# 07_ZYNQ_DDR.net
KiCad netlist of a schematic drawn in Altium Designer
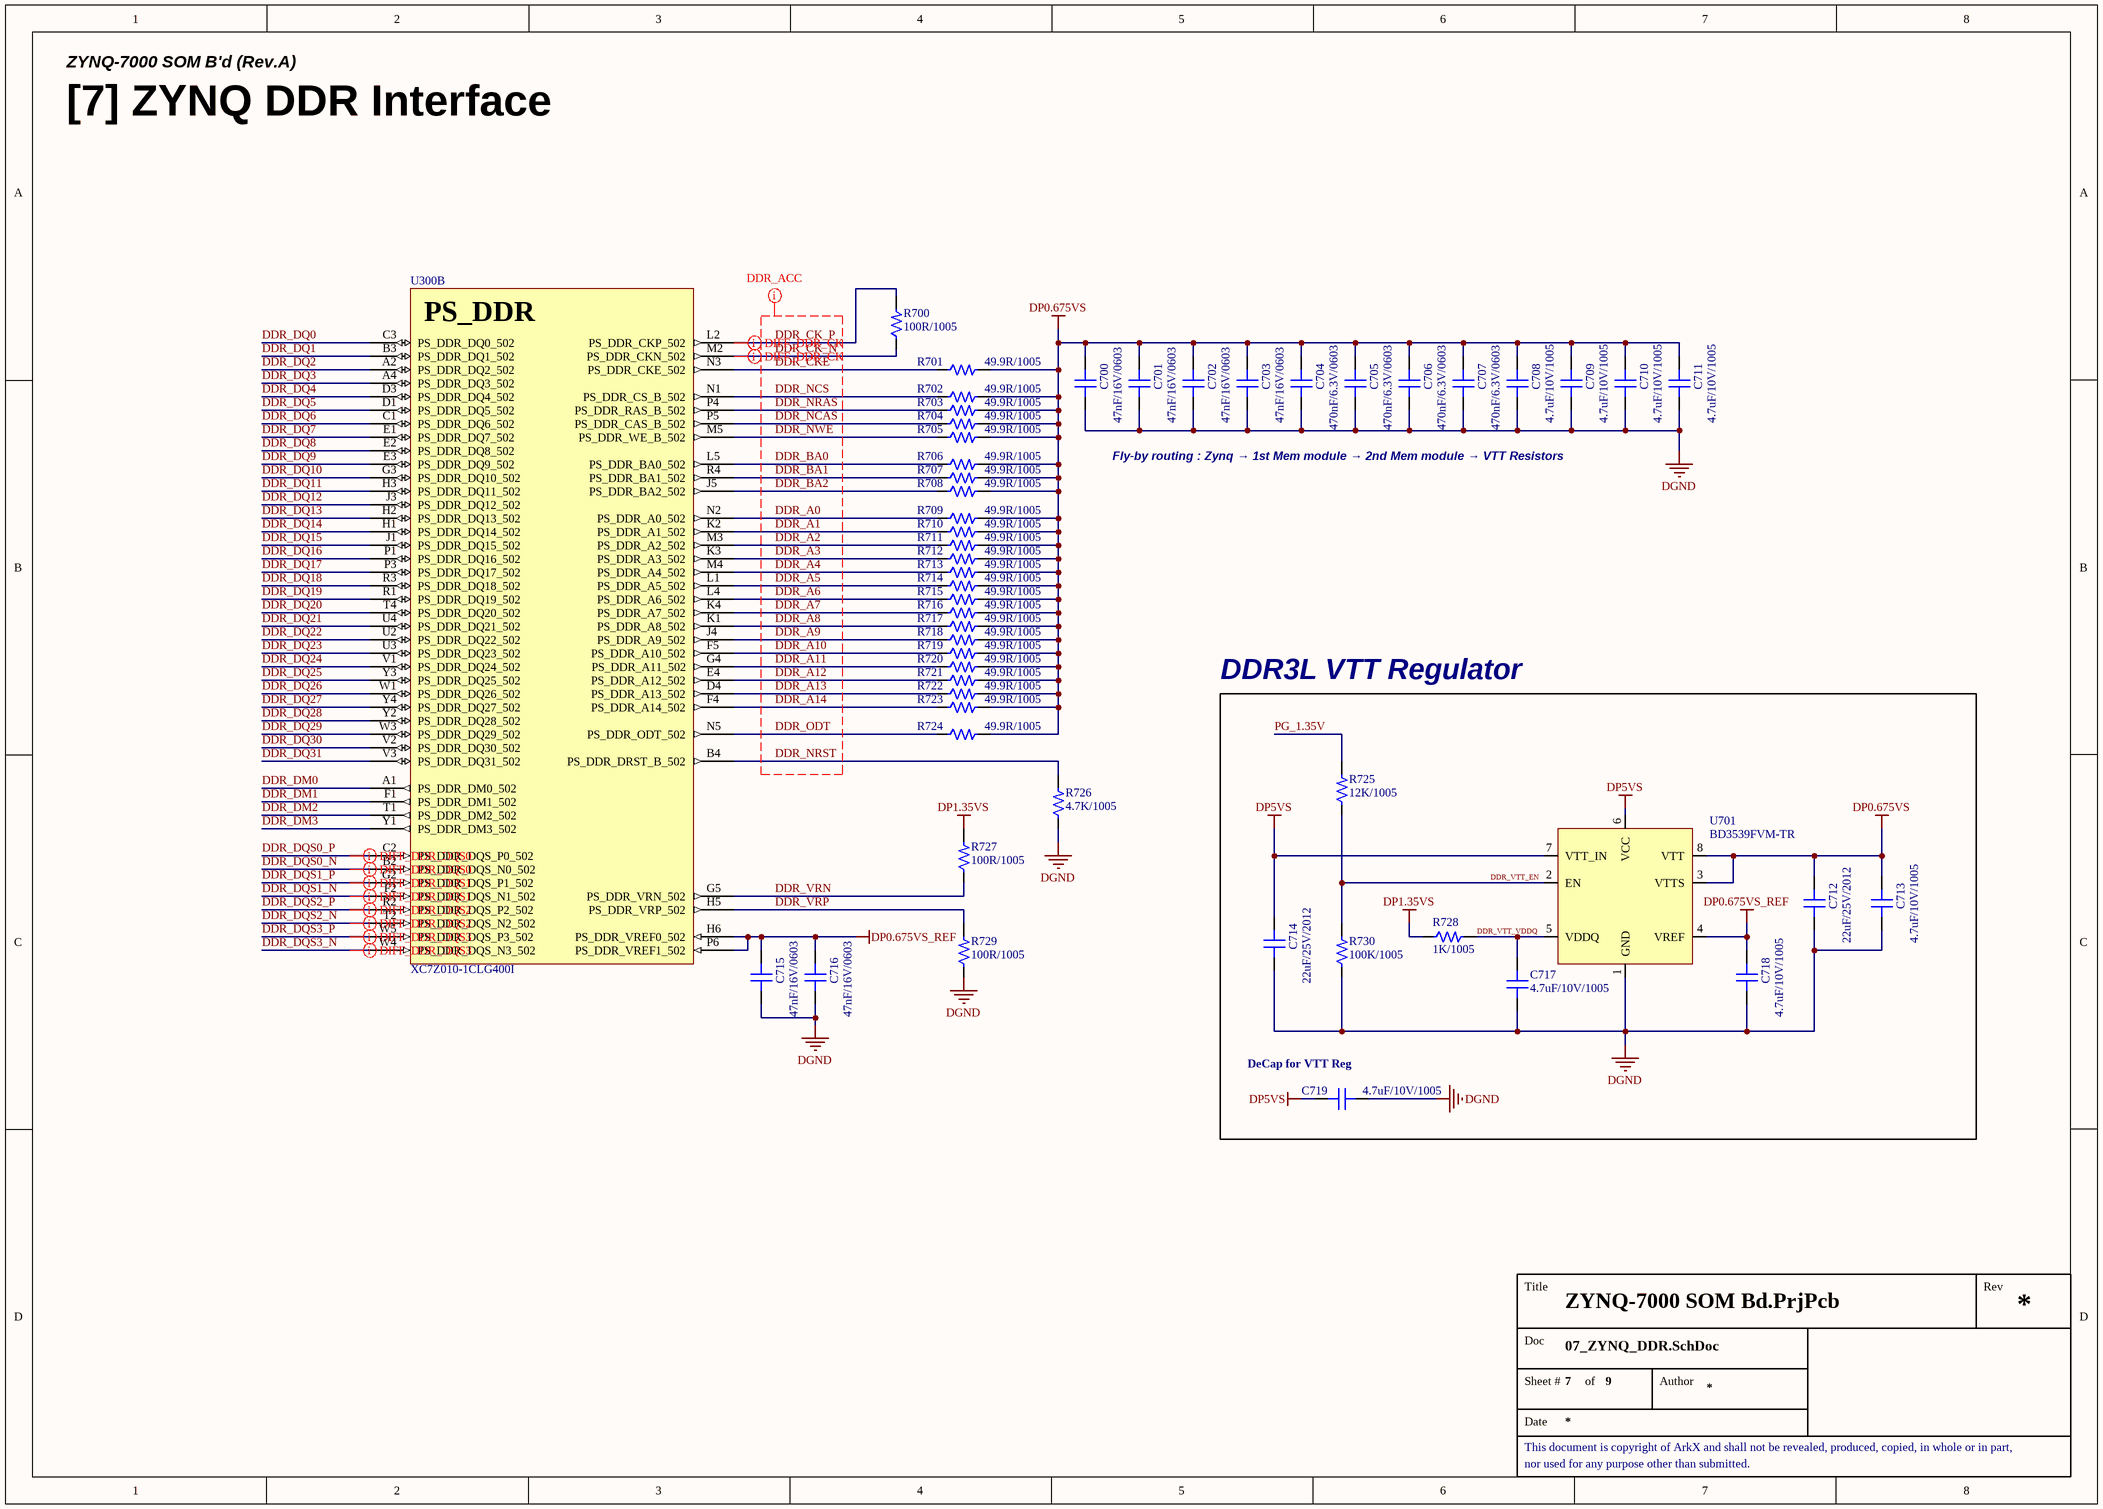
[diagram p0: 07_ZYNQ_DDR.SchDoc]

(export (version "E")
  (design (tool "Eeschema 10.0.6"))
  (components
    (comp (ref "C700")
      (value "47nF/16V/0603")
      (footprint "CAP 0603 (0201_INCH)")
      (description "16V 47nF X5R ±10% 0201 Multilayer Ceramic Capacitors MLCC - SMD/SMT ROHS")
      (fields (field (name "LCSC PART #") "C88917"))
      (libsource (lib "Arkx") (part "CAP_47nF/16V/0603"))
    )
    (comp (ref "C701")
      (value "47nF/16V/0603")
      (footprint "CAP 0603 (0201_INCH)")
      (description "16V 47nF X5R ±10% 0201 Multilayer Ceramic Capacitors MLCC - SMD/SMT ROHS")
      (fields (field (name "LCSC PART #") "C88917"))
      (libsource (lib "Arkx") (part "CAP_47nF/16V/0603"))
    )
    (comp (ref "C702")
      (value "47nF/16V/0603")
      (footprint "CAP 0603 (0201_INCH)")
      (description "16V 47nF X5R ±10% 0201 Multilayer Ceramic Capacitors MLCC - SMD/SMT ROHS")
      (fields (field (name "LCSC PART #") "C88917"))
      (libsource (lib "Arkx") (part "CAP_47nF/16V/0603"))
    )
    (comp (ref "C703")
      (value "47nF/16V/0603")
      (footprint "CAP 0603 (0201_INCH)")
      (description "16V 47nF X5R ±10% 0201 Multilayer Ceramic Capacitors MLCC - SMD/SMT ROHS")
      (fields (field (name "LCSC PART #") "C88917"))
      (libsource (lib "Arkx") (part "CAP_47nF/16V/0603"))
    )
    (comp (ref "C704")
      (value "470nF/6.3V/0603")
      (footprint "CAP 0603 (0201_INCH)")
      (description "6.3V 470nF X5R ±10% 0201  Multilayer Ceramic Capacitors MLCC - SMD/SMT ROHS")
      (fields (field (name "LCSC PART #") "C85926"))
      (libsource (lib "Arkx") (part "CAP_470nF/6.3V/0603"))
    )
    (comp (ref "C705")
      (value "470nF/6.3V/0603")
      (footprint "CAP 0603 (0201_INCH)")
      (description "6.3V 470nF X5R ±10% 0201  Multilayer Ceramic Capacitors MLCC - SMD/SMT ROHS")
      (fields (field (name "LCSC PART #") "C85926"))
      (libsource (lib "Arkx") (part "CAP_470nF/6.3V/0603"))
    )
    (comp (ref "C706")
      (value "470nF/6.3V/0603")
      (footprint "CAP 0603 (0201_INCH)")
      (description "6.3V 470nF X5R ±10% 0201  Multilayer Ceramic Capacitors MLCC - SMD/SMT ROHS")
      (fields (field (name "LCSC PART #") "C85926"))
      (libsource (lib "Arkx") (part "CAP_470nF/6.3V/0603"))
    )
    (comp (ref "C707")
      (value "470nF/6.3V/0603")
      (footprint "CAP 0603 (0201_INCH)")
      (description "6.3V 470nF X5R ±10% 0201  Multilayer Ceramic Capacitors MLCC - SMD/SMT ROHS")
      (fields (field (name "LCSC PART #") "C85926"))
      (libsource (lib "Arkx") (part "CAP_470nF/6.3V/0603"))
    )
    (comp (ref "C708")
      (value "4.7uF/10V/1005")
      (footprint "CAP 1005 (0402_INCH)")
      (description "10V 4.7uF X5R ±20% 0402  Multilayer Ceramic Capacitors MLCC - SMD/SMT ROHS")
      (fields (field (name "LCSC PART #") "C23733"))
      (libsource (lib "Arkx") (part "CAP_4.7uF/10V/1005"))
    )
    (comp (ref "C709")
      (value "4.7uF/10V/1005")
      (footprint "CAP 1005 (0402_INCH)")
      (description "10V 4.7uF X5R ±20% 0402  Multilayer Ceramic Capacitors MLCC - SMD/SMT ROHS")
      (fields (field (name "LCSC PART #") "C23733"))
      (libsource (lib "Arkx") (part "CAP_4.7uF/10V/1005"))
    )
    (comp (ref "C710")
      (value "4.7uF/10V/1005")
      (footprint "CAP 1005 (0402_INCH)")
      (description "10V 4.7uF X5R ±20% 0402  Multilayer Ceramic Capacitors MLCC - SMD/SMT ROHS")
      (fields (field (name "LCSC PART #") "C23733"))
      (libsource (lib "Arkx") (part "CAP_4.7uF/10V/1005"))
    )
    (comp (ref "C711")
      (value "4.7uF/10V/1005")
      (footprint "CAP 1005 (0402_INCH)")
      (description "10V 4.7uF X5R ±20% 0402  Multilayer Ceramic Capacitors MLCC - SMD/SMT ROHS")
      (fields (field (name "LCSC PART #") "C23733"))
      (libsource (lib "Arkx") (part "CAP_4.7uF/10V/1005"))
    )
    (comp (ref "C712")
      (value "22uF/25V/2012")
      (footprint "CAP 2012 (0805_INCH)")
      (description "Ceramic CAP_22uF/25V/2012")
      (fields (field (name "LCSC PART #") "C45783"))
      (libsource (lib "Arkx") (part "CAP_22uF/25V/2012"))
    )
    (comp (ref "C713")
      (value "4.7uF/10V/1005")
      (footprint "CAP 1005 (0402_INCH)")
      (description "10V 4.7uF X5R ±20% 0402  Multilayer Ceramic Capacitors MLCC - SMD/SMT ROHS")
      (fields (field (name "LCSC PART #") "C23733"))
      (libsource (lib "Arkx") (part "CAP_4.7uF/10V/1005"))
    )
    (comp (ref "C714")
      (value "22uF/25V/2012")
      (footprint "CAP 2012 (0805_INCH)")
      (description "Ceramic CAP_22uF/25V/2012")
      (fields (field (name "LCSC PART #") "C45783"))
      (libsource (lib "Arkx") (part "CAP_22uF/25V/2012"))
    )
    (comp (ref "C715")
      (value "47nF/16V/0603")
      (footprint "CAP 0603 (0201_INCH)")
      (description "16V 47nF X5R ±10% 0201 Multilayer Ceramic Capacitors MLCC - SMD/SMT ROHS")
      (fields (field (name "LCSC PART #") "C88917"))
      (libsource (lib "Arkx") (part "CAP_47nF/16V/0603"))
    )
    (comp (ref "C716")
      (value "47nF/16V/0603")
      (footprint "CAP 0603 (0201_INCH)")
      (description "16V 47nF X5R ±10% 0201 Multilayer Ceramic Capacitors MLCC - SMD/SMT ROHS")
      (fields (field (name "LCSC PART #") "C88917"))
      (libsource (lib "Arkx") (part "CAP_47nF/16V/0603"))
    )
    (comp (ref "C717")
      (value "4.7uF/10V/1005")
      (footprint "CAP 1005 (0402_INCH)")
      (description "10V 4.7uF X5R ±20% 0402  Multilayer Ceramic Capacitors MLCC - SMD/SMT ROHS")
      (fields (field (name "LCSC PART #") "C23733"))
      (libsource (lib "Arkx") (part "CAP_4.7uF/10V/1005"))
    )
    (comp (ref "C718")
      (value "4.7uF/10V/1005")
      (footprint "CAP 1005 (0402_INCH)")
      (description "10V 4.7uF X5R ±20% 0402  Multilayer Ceramic Capacitors MLCC - SMD/SMT ROHS")
      (fields (field (name "LCSC PART #") "C23733"))
      (libsource (lib "Arkx") (part "CAP_4.7uF/10V/1005"))
    )
    (comp (ref "C719")
      (value "4.7uF/10V/1005")
      (footprint "CAP 1005 (0402_INCH)")
      (description "10V 4.7uF X5R ±20% 0402  Multilayer Ceramic Capacitors MLCC - SMD/SMT ROHS")
      (fields (field (name "LCSC PART #") "C23733"))
      (libsource (lib "Arkx") (part "CAP_4.7uF/10V/1005"))
    )
    (comp (ref "R700")
      (value "100R/1005")
      (footprint "RES 1005 (0402_inch)")
      (description "RES_100R/1005/62.5mW")
      (fields (field (name "LCSC PART #") "C25076"))
      (libsource (lib "Arkx") (part "RES_100R/1005/62.5mW"))
    )
    (comp (ref "R701")
      (value "49.9R/1005")
      (footprint "RES 1005 (0402_inch)")
      (description "RES_49.9R/1005/62.5mW")
      (fields (field (name "LCSC PART #") "C25120"))
      (libsource (lib "Arkx") (part "RES_49.9R/1005/62.5mW"))
    )
    (comp (ref "R702")
      (value "49.9R/1005")
      (footprint "RES 1005 (0402_inch)")
      (description "RES_49.9R/1005/62.5mW")
      (fields (field (name "LCSC PART #") "C25120"))
      (libsource (lib "Arkx") (part "RES_49.9R/1005/62.5mW"))
    )
    (comp (ref "R703")
      (value "49.9R/1005")
      (footprint "RES 1005 (0402_inch)")
      (description "RES_49.9R/1005/62.5mW")
      (fields (field (name "LCSC PART #") "C25120"))
      (libsource (lib "Arkx") (part "RES_49.9R/1005/62.5mW"))
    )
    (comp (ref "R704")
      (value "49.9R/1005")
      (footprint "RES 1005 (0402_inch)")
      (description "RES_49.9R/1005/62.5mW")
      (fields (field (name "LCSC PART #") "C25120"))
      (libsource (lib "Arkx") (part "RES_49.9R/1005/62.5mW"))
    )
    (comp (ref "R705")
      (value "49.9R/1005")
      (footprint "RES 1005 (0402_inch)")
      (description "RES_49.9R/1005/62.5mW")
      (fields (field (name "LCSC PART #") "C25120"))
      (libsource (lib "Arkx") (part "RES_49.9R/1005/62.5mW"))
    )
    (comp (ref "R706")
      (value "49.9R/1005")
      (footprint "RES 1005 (0402_inch)")
      (description "RES_49.9R/1005/62.5mW")
      (fields (field (name "LCSC PART #") "C25120"))
      (libsource (lib "Arkx") (part "RES_49.9R/1005/62.5mW"))
    )
    (comp (ref "R707")
      (value "49.9R/1005")
      (footprint "RES 1005 (0402_inch)")
      (description "RES_49.9R/1005/62.5mW")
      (fields (field (name "LCSC PART #") "C25120"))
      (libsource (lib "Arkx") (part "RES_49.9R/1005/62.5mW"))
    )
    (comp (ref "R708")
      (value "49.9R/1005")
      (footprint "RES 1005 (0402_inch)")
      (description "RES_49.9R/1005/62.5mW")
      (fields (field (name "LCSC PART #") "C25120"))
      (libsource (lib "Arkx") (part "RES_49.9R/1005/62.5mW"))
    )
    (comp (ref "R709")
      (value "49.9R/1005")
      (footprint "RES 1005 (0402_inch)")
      (description "RES_49.9R/1005/62.5mW")
      (fields (field (name "LCSC PART #") "C25120"))
      (libsource (lib "Arkx") (part "RES_49.9R/1005/62.5mW"))
    )
    (comp (ref "R710")
      (value "49.9R/1005")
      (footprint "RES 1005 (0402_inch)")
      (description "RES_49.9R/1005/62.5mW")
      (fields (field (name "LCSC PART #") "C25120"))
      (libsource (lib "Arkx") (part "RES_49.9R/1005/62.5mW"))
    )
    (comp (ref "R711")
      (value "49.9R/1005")
      (footprint "RES 1005 (0402_inch)")
      (description "RES_49.9R/1005/62.5mW")
      (fields (field (name "LCSC PART #") "C25120"))
      (libsource (lib "Arkx") (part "RES_49.9R/1005/62.5mW"))
    )
    (comp (ref "R712")
      (value "49.9R/1005")
      (footprint "RES 1005 (0402_inch)")
      (description "RES_49.9R/1005/62.5mW")
      (fields (field (name "LCSC PART #") "C25120"))
      (libsource (lib "Arkx") (part "RES_49.9R/1005/62.5mW"))
    )
    (comp (ref "R713")
      (value "49.9R/1005")
      (footprint "RES 1005 (0402_inch)")
      (description "RES_49.9R/1005/62.5mW")
      (fields (field (name "LCSC PART #") "C25120"))
      (libsource (lib "Arkx") (part "RES_49.9R/1005/62.5mW"))
    )
    (comp (ref "R714")
      (value "49.9R/1005")
      (footprint "RES 1005 (0402_inch)")
      (description "RES_49.9R/1005/62.5mW")
      (fields (field (name "LCSC PART #") "C25120"))
      (libsource (lib "Arkx") (part "RES_49.9R/1005/62.5mW"))
    )
    (comp (ref "R715")
      (value "49.9R/1005")
      (footprint "RES 1005 (0402_inch)")
      (description "RES_49.9R/1005/62.5mW")
      (fields (field (name "LCSC PART #") "C25120"))
      (libsource (lib "Arkx") (part "RES_49.9R/1005/62.5mW"))
    )
    (comp (ref "R716")
      (value "49.9R/1005")
      (footprint "RES 1005 (0402_inch)")
      (description "RES_49.9R/1005/62.5mW")
      (fields (field (name "LCSC PART #") "C25120"))
      (libsource (lib "Arkx") (part "RES_49.9R/1005/62.5mW"))
    )
    (comp (ref "R717")
      (value "49.9R/1005")
      (footprint "RES 1005 (0402_inch)")
      (description "RES_49.9R/1005/62.5mW")
      (fields (field (name "LCSC PART #") "C25120"))
      (libsource (lib "Arkx") (part "RES_49.9R/1005/62.5mW"))
    )
    (comp (ref "R718")
      (value "49.9R/1005")
      (footprint "RES 1005 (0402_inch)")
      (description "RES_49.9R/1005/62.5mW")
      (fields (field (name "LCSC PART #") "C25120"))
      (libsource (lib "Arkx") (part "RES_49.9R/1005/62.5mW"))
    )
    (comp (ref "R719")
      (value "49.9R/1005")
      (footprint "RES 1005 (0402_inch)")
      (description "RES_49.9R/1005/62.5mW")
      (fields (field (name "LCSC PART #") "C25120"))
      (libsource (lib "Arkx") (part "RES_49.9R/1005/62.5mW"))
    )
    (comp (ref "R720")
      (value "49.9R/1005")
      (footprint "RES 1005 (0402_inch)")
      (description "RES_49.9R/1005/62.5mW")
      (fields (field (name "LCSC PART #") "C25120"))
      (libsource (lib "Arkx") (part "RES_49.9R/1005/62.5mW"))
    )
    (comp (ref "R721")
      (value "49.9R/1005")
      (footprint "RES 1005 (0402_inch)")
      (description "RES_49.9R/1005/62.5mW")
      (fields (field (name "LCSC PART #") "C25120"))
      (libsource (lib "Arkx") (part "RES_49.9R/1005/62.5mW"))
    )
    (comp (ref "R722")
      (value "49.9R/1005")
      (footprint "RES 1005 (0402_inch)")
      (description "RES_49.9R/1005/62.5mW")
      (fields (field (name "LCSC PART #") "C25120"))
      (libsource (lib "Arkx") (part "RES_49.9R/1005/62.5mW"))
    )
    (comp (ref "R723")
      (value "49.9R/1005")
      (footprint "RES 1005 (0402_inch)")
      (description "RES_49.9R/1005/62.5mW")
      (fields (field (name "LCSC PART #") "C25120"))
      (libsource (lib "Arkx") (part "RES_49.9R/1005/62.5mW"))
    )
    (comp (ref "R724")
      (value "49.9R/1005")
      (footprint "RES 1005 (0402_inch)")
      (description "RES_49.9R/1005/62.5mW")
      (fields (field (name "LCSC PART #") "C25120"))
      (libsource (lib "Arkx") (part "RES_49.9R/1005/62.5mW"))
    )
    (comp (ref "R725")
      (value "12K/1005")
      (footprint "RES 1005 (0402_inch)")
      (description "RES_12K/1005/62.5mW")
      (fields (field (name "LCSC PART #") "C25752"))
      (libsource (lib "Arkx") (part "RES_12K/1005/62.5mW"))
    )
    (comp (ref "R726")
      (value "4.7K/1005")
      (footprint "RES 1005 (0402_inch)")
      (description "RES_4.7K/1005/62.5mW")
      (fields (field (name "LCSC PART #") "C25900"))
      (libsource (lib "Arkx") (part "RES_4.7K/1005/62.5mW"))
    )
    (comp (ref "R727")
      (value "100R/1005")
      (footprint "RES 1005 (0402_inch)")
      (description "RES_100R/1005/62.5mW")
      (fields (field (name "LCSC PART #") "C25076"))
      (libsource (lib "Arkx") (part "RES_100R/1005/62.5mW"))
    )
    (comp (ref "R728")
      (value "1K/1005")
      (footprint "RES 1005 (0402_inch)")
      (description "RES_1K/1005/62.5mW")
      (fields (field (name "LCSC PART #") "C11702"))
      (libsource (lib "Arkx") (part "RES_1K/1005/62.5mW"))
    )
    (comp (ref "R729")
      (value "100R/1005")
      (footprint "RES 1005 (0402_inch)")
      (description "RES_100R/1005/62.5mW")
      (fields (field (name "LCSC PART #") "C25076"))
      (libsource (lib "Arkx") (part "RES_100R/1005/62.5mW"))
    )
    (comp (ref "R730")
      (value "100K/1005")
      (footprint "RES 1005 (0402_inch)")
      (description "RES_100K/1005/62.5mW")
      (fields (field (name "LCSC PART #") "C25741"))
      (libsource (lib "Arkx") (part "RES_100K/1005/62.5mW"))
    )
    (comp (ref "U300")
      (value "XC7Z010-1CLG400I")
      (footprint "IC_SOC_XC7Z010-1CLG400I")
      (fields (field (name "LCSC PART #") "C2840994"))
      (libsource (lib "Arkx") (part "IC_SOC_XC7Z010-1CLG400I"))
    )
    (comp (ref "U701")
      (value "BD3539FVM-TR")
      (footprint "IC_MSOP-8")
      (description "1.0V to 5.5V, 1A 1ch\r\nTermination Regulators for DDR-SDRAMs, 8-MSOP")
      (fields (field (name "LCSC PART #") "C213437"))
      (libsource (lib "Arkx") (part "IC_REG_VTT_BD3539FVM-TR"))
    )
  )
  (nets
    (net (code "1") (name "/DDR_A0") (class "Default")
      (node (ref "R709") (pin "1") (pinfunction "1_1") (pintype "passive"))
      (node (ref "U300") (pin "N2") (pinfunction "PS_DDR_A0_502_N2") (pintype "output"))
    )
    (net (code "2") (name "/DDR_A1") (class "Default")
      (node (ref "R710") (pin "1") (pinfunction "1_1") (pintype "passive"))
      (node (ref "U300") (pin "K2") (pinfunction "PS_DDR_A1_502_K2") (pintype "output"))
    )
    (net (code "3") (name "/DDR_A2") (class "Default")
      (node (ref "R711") (pin "1") (pinfunction "1_1") (pintype "passive"))
      (node (ref "U300") (pin "M3") (pinfunction "PS_DDR_A2_502_M3") (pintype "output"))
    )
    (net (code "4") (name "/DDR_A3") (class "Default")
      (node (ref "R712") (pin "1") (pinfunction "1_1") (pintype "passive"))
      (node (ref "U300") (pin "K3") (pinfunction "PS_DDR_A3_502_K3") (pintype "output"))
    )
    (net (code "5") (name "/DDR_A4") (class "Default")
      (node (ref "R713") (pin "1") (pinfunction "1_1") (pintype "passive"))
      (node (ref "U300") (pin "M4") (pinfunction "PS_DDR_A4_502_M4") (pintype "output"))
    )
    (net (code "6") (name "/DDR_A5") (class "Default")
      (node (ref "R714") (pin "1") (pinfunction "1_1") (pintype "passive"))
      (node (ref "U300") (pin "L1") (pinfunction "PS_DDR_A5_502_L1") (pintype "output"))
    )
    (net (code "7") (name "/DDR_A6") (class "Default")
      (node (ref "R715") (pin "1") (pinfunction "1_1") (pintype "passive"))
      (node (ref "U300") (pin "L4") (pinfunction "PS_DDR_A6_502_L4") (pintype "output"))
    )
    (net (code "8") (name "/DDR_A7") (class "Default")
      (node (ref "R716") (pin "1") (pinfunction "1_1") (pintype "passive"))
      (node (ref "U300") (pin "K4") (pinfunction "PS_DDR_A7_502_K4") (pintype "output"))
    )
    (net (code "9") (name "/DDR_A8") (class "Default")
      (node (ref "R717") (pin "1") (pinfunction "1_1") (pintype "passive"))
      (node (ref "U300") (pin "K1") (pinfunction "PS_DDR_A8_502_K1") (pintype "output"))
    )
    (net (code "10") (name "/DDR_A9") (class "Default")
      (node (ref "R718") (pin "1") (pinfunction "1_1") (pintype "passive"))
      (node (ref "U300") (pin "J4") (pinfunction "PS_DDR_A9_502_J4") (pintype "output"))
    )
    (net (code "11") (name "/DDR_A10") (class "Default")
      (node (ref "R719") (pin "1") (pinfunction "1_1") (pintype "passive"))
      (node (ref "U300") (pin "F5") (pinfunction "PS_DDR_A10_502_F5") (pintype "output"))
    )
    (net (code "12") (name "/DDR_A11") (class "Default")
      (node (ref "R720") (pin "1") (pinfunction "1_1") (pintype "passive"))
      (node (ref "U300") (pin "G4") (pinfunction "PS_DDR_A11_502_G4") (pintype "output"))
    )
    (net (code "13") (name "/DDR_A12") (class "Default")
      (node (ref "R721") (pin "1") (pinfunction "1_1") (pintype "passive"))
      (node (ref "U300") (pin "E4") (pinfunction "PS_DDR_A12_502_E4") (pintype "output"))
    )
    (net (code "14") (name "/DDR_A13") (class "Default")
      (node (ref "R722") (pin "1") (pinfunction "1_1") (pintype "passive"))
      (node (ref "U300") (pin "D4") (pinfunction "PS_DDR_A13_502_D4") (pintype "output"))
    )
    (net (code "15") (name "/DDR_A14") (class "Default")
      (node (ref "R723") (pin "1") (pinfunction "1_1") (pintype "passive"))
      (node (ref "U300") (pin "F4") (pinfunction "PS_DDR_A14_502_F4") (pintype "output"))
    )
    (net (code "16") (name "/DDR_BA0") (class "Default")
      (node (ref "R706") (pin "1") (pinfunction "1_1") (pintype "passive"))
      (node (ref "U300") (pin "L5") (pinfunction "PS_DDR_BA0_502_L5") (pintype "output"))
    )
    (net (code "17") (name "/DDR_BA1") (class "Default")
      (node (ref "R707") (pin "1") (pinfunction "1_1") (pintype "passive"))
      (node (ref "U300") (pin "R4") (pinfunction "PS_DDR_BA1_502_R4") (pintype "output"))
    )
    (net (code "18") (name "/DDR_BA2") (class "Default")
      (node (ref "R708") (pin "1") (pinfunction "1_1") (pintype "passive"))
      (node (ref "U300") (pin "J5") (pinfunction "PS_DDR_BA2_502_J5") (pintype "output"))
    )
    (net (code "19") (name "/DDR_CKE") (class "Default")
      (node (ref "R701") (pin "1") (pinfunction "1_1") (pintype "passive"))
      (node (ref "U300") (pin "N3") (pinfunction "PS_DDR_CKE_502_N3") (pintype "output"))
    )
    (net (code "20") (name "/DDR_CK_N") (class "Default")
      (node (ref "R700") (pin "1") (pinfunction "1_1") (pintype "passive"))
      (node (ref "U300") (pin "M2") (pinfunction "PS_DDR_CKN_502_M2") (pintype "output"))
    )
    (net (code "21") (name "/DDR_CK_P") (class "Default")
      (node (ref "R700") (pin "2") (pinfunction "2_2") (pintype "passive"))
      (node (ref "U300") (pin "L2") (pinfunction "PS_DDR_CKP_502_L2") (pintype "output"))
    )
    (net (code "22") (name "/DDR_DM0") (class "Default")
      (node (ref "U300") (pin "A1") (pinfunction "PS_DDR_DM0_502_A1") (pintype "output"))
    )
    (net (code "23") (name "/DDR_DM1") (class "Default")
      (node (ref "U300") (pin "F1") (pinfunction "PS_DDR_DM1_502_F1") (pintype "output"))
    )
    (net (code "24") (name "/DDR_DM2") (class "Default")
      (node (ref "U300") (pin "T1") (pinfunction "PS_DDR_DM2_502_T1") (pintype "output"))
    )
    (net (code "25") (name "/DDR_DM3") (class "Default")
      (node (ref "U300") (pin "Y1") (pinfunction "PS_DDR_DM3_502_Y1") (pintype "output"))
    )
    (net (code "26") (name "/DDR_DQ0") (class "Default")
      (node (ref "U300") (pin "C3") (pinfunction "PS_DDR_DQ0_502_C3") (pintype "bidirectional"))
    )
    (net (code "27") (name "/DDR_DQ1") (class "Default")
      (node (ref "U300") (pin "B3") (pinfunction "PS_DDR_DQ1_502_B3") (pintype "bidirectional"))
    )
    (net (code "28") (name "/DDR_DQ2") (class "Default")
      (node (ref "U300") (pin "A2") (pinfunction "PS_DDR_DQ2_502_A2") (pintype "bidirectional"))
    )
    (net (code "29") (name "/DDR_DQ3") (class "Default")
      (node (ref "U300") (pin "A4") (pinfunction "PS_DDR_DQ3_502_A4") (pintype "bidirectional"))
    )
    (net (code "30") (name "/DDR_DQ4") (class "Default")
      (node (ref "U300") (pin "D3") (pinfunction "PS_DDR_DQ4_502_D3") (pintype "bidirectional"))
    )
    (net (code "31") (name "/DDR_DQ5") (class "Default")
      (node (ref "U300") (pin "D1") (pinfunction "PS_DDR_DQ5_502_D1") (pintype "bidirectional"))
    )
    (net (code "32") (name "/DDR_DQ6") (class "Default")
      (node (ref "U300") (pin "C1") (pinfunction "PS_DDR_DQ6_502_C1") (pintype "bidirectional"))
    )
    (net (code "33") (name "/DDR_DQ7") (class "Default")
      (node (ref "U300") (pin "E1") (pinfunction "PS_DDR_DQ7_502_E1") (pintype "bidirectional"))
    )
    (net (code "34") (name "/DDR_DQ8") (class "Default")
      (node (ref "U300") (pin "E2") (pinfunction "PS_DDR_DQ8_502_E2") (pintype "bidirectional"))
    )
    (net (code "35") (name "/DDR_DQ9") (class "Default")
      (node (ref "U300") (pin "E3") (pinfunction "PS_DDR_DQ9_502_E3") (pintype "bidirectional"))
    )
    (net (code "36") (name "/DDR_DQ10") (class "Default")
      (node (ref "U300") (pin "G3") (pinfunction "PS_DDR_DQ10_502_G3") (pintype "bidirectional"))
    )
    (net (code "37") (name "/DDR_DQ11") (class "Default")
      (node (ref "U300") (pin "H3") (pinfunction "PS_DDR_DQ11_502_H3") (pintype "bidirectional"))
    )
    (net (code "38") (name "/DDR_DQ12") (class "Default")
      (node (ref "U300") (pin "J3") (pinfunction "PS_DDR_DQ12_502_J3") (pintype "bidirectional"))
    )
    (net (code "39") (name "/DDR_DQ13") (class "Default")
      (node (ref "U300") (pin "H2") (pinfunction "PS_DDR_DQ13_502_H2") (pintype "bidirectional"))
    )
    (net (code "40") (name "/DDR_DQ14") (class "Default")
      (node (ref "U300") (pin "H1") (pinfunction "PS_DDR_DQ14_502_H1") (pintype "bidirectional"))
    )
    (net (code "41") (name "/DDR_DQ15") (class "Default")
      (node (ref "U300") (pin "J1") (pinfunction "PS_DDR_DQ15_502_J1") (pintype "bidirectional"))
    )
    (net (code "42") (name "/DDR_DQ16") (class "Default")
      (node (ref "U300") (pin "P1") (pinfunction "PS_DDR_DQ16_502_P1") (pintype "bidirectional"))
    )
    (net (code "43") (name "/DDR_DQ17") (class "Default")
      (node (ref "U300") (pin "P3") (pinfunction "PS_DDR_DQ17_502_P3") (pintype "bidirectional"))
    )
    (net (code "44") (name "/DDR_DQ18") (class "Default")
      (node (ref "U300") (pin "R3") (pinfunction "PS_DDR_DQ18_502_R3") (pintype "bidirectional"))
    )
    (net (code "45") (name "/DDR_DQ19") (class "Default")
      (node (ref "U300") (pin "R1") (pinfunction "PS_DDR_DQ19_502_R1") (pintype "bidirectional"))
    )
    (net (code "46") (name "/DDR_DQ20") (class "Default")
      (node (ref "U300") (pin "T4") (pinfunction "PS_DDR_DQ20_502_T4") (pintype "bidirectional"))
    )
    (net (code "47") (name "/DDR_DQ21") (class "Default")
      (node (ref "U300") (pin "U4") (pinfunction "PS_DDR_DQ21_502_U4") (pintype "bidirectional"))
    )
    (net (code "48") (name "/DDR_DQ22") (class "Default")
      (node (ref "U300") (pin "U2") (pinfunction "PS_DDR_DQ22_502_U2") (pintype "bidirectional"))
    )
    (net (code "49") (name "/DDR_DQ23") (class "Default")
      (node (ref "U300") (pin "U3") (pinfunction "PS_DDR_DQ23_502_U3") (pintype "bidirectional"))
    )
    (net (code "50") (name "/DDR_DQ24") (class "Default")
      (node (ref "U300") (pin "V1") (pinfunction "PS_DDR_DQ24_502_V1") (pintype "bidirectional"))
    )
    (net (code "51") (name "/DDR_DQ25") (class "Default")
      (node (ref "U300") (pin "Y3") (pinfunction "PS_DDR_DQ25_502_Y3") (pintype "bidirectional"))
    )
    (net (code "52") (name "/DDR_DQ26") (class "Default")
      (node (ref "U300") (pin "W1") (pinfunction "PS_DDR_DQ26_502_W1") (pintype "bidirectional"))
    )
    (net (code "53") (name "/DDR_DQ27") (class "Default")
      (node (ref "U300") (pin "Y4") (pinfunction "PS_DDR_DQ27_502_Y4") (pintype "bidirectional"))
    )
    (net (code "54") (name "/DDR_DQ28") (class "Default")
      (node (ref "U300") (pin "Y2") (pinfunction "PS_DDR_DQ28_502_Y2") (pintype "bidirectional"))
    )
    (net (code "55") (name "/DDR_DQ29") (class "Default")
      (node (ref "U300") (pin "W3") (pinfunction "PS_DDR_DQ29_502_W3") (pintype "bidirectional"))
    )
    (net (code "56") (name "/DDR_DQ30") (class "Default")
      (node (ref "U300") (pin "V2") (pinfunction "PS_DDR_DQ30_502_V2") (pintype "bidirectional"))
    )
    (net (code "57") (name "/DDR_DQ31") (class "Default")
      (node (ref "U300") (pin "V3") (pinfunction "PS_DDR_DQ31_502_V3") (pintype "bidirectional"))
    )
    (net (code "58") (name "/DDR_DQS0_N") (class "Default")
      (node (ref "U300") (pin "B2") (pinfunction "PS_DDR_DQS_N0_502_B2") (pintype "input"))
    )
    (net (code "59") (name "/DDR_DQS0_P") (class "Default")
      (node (ref "U300") (pin "C2") (pinfunction "PS_DDR_DQS_P0_502_C2") (pintype "input"))
    )
    (net (code "60") (name "/DDR_DQS1_N") (class "Default")
      (node (ref "U300") (pin "F2") (pinfunction "PS_DDR_DQS_N1_502_F2") (pintype "input"))
    )
    (net (code "61") (name "/DDR_DQS1_P") (class "Default")
      (node (ref "U300") (pin "G2") (pinfunction "PS_DDR_DQS_P1_502_G2") (pintype "input"))
    )
    (net (code "62") (name "/DDR_DQS2_N") (class "Default")
      (node (ref "U300") (pin "T2") (pinfunction "PS_DDR_DQS_N2_502_T2") (pintype "input"))
    )
    (net (code "63") (name "/DDR_DQS2_P") (class "Default")
      (node (ref "U300") (pin "R2") (pinfunction "PS_DDR_DQS_P2_502_R2") (pintype "input"))
    )
    (net (code "64") (name "/DDR_DQS3_N") (class "Default")
      (node (ref "U300") (pin "W4") (pinfunction "PS_DDR_DQS_N3_502_W4") (pintype "input"))
    )
    (net (code "65") (name "/DDR_DQS3_P") (class "Default")
      (node (ref "U300") (pin "W5") (pinfunction "PS_DDR_DQS_P3_502_W5") (pintype "input"))
    )
    (net (code "66") (name "/DDR_NCAS") (class "Default")
      (node (ref "R704") (pin "1") (pinfunction "1_1") (pintype "passive"))
      (node (ref "U300") (pin "P5") (pinfunction "PS_DDR_CAS_B_502_P5") (pintype "output"))
    )
    (net (code "67") (name "/DDR_NCS") (class "Default")
      (node (ref "R702") (pin "1") (pinfunction "1_1") (pintype "passive"))
      (node (ref "U300") (pin "N1") (pinfunction "PS_DDR_CS_B_502_N1") (pintype "output"))
    )
    (net (code "68") (name "/DDR_NRAS") (class "Default")
      (node (ref "R703") (pin "1") (pinfunction "1_1") (pintype "passive"))
      (node (ref "U300") (pin "P4") (pinfunction "PS_DDR_RAS_B_502_P4") (pintype "output"))
    )
    (net (code "69") (name "/DDR_NRST") (class "Default")
      (node (ref "R726") (pin "2") (pinfunction "2_2") (pintype "passive"))
      (node (ref "U300") (pin "B4") (pinfunction "PS_DDR_DRST_B_502_B4") (pintype "output"))
    )
    (net (code "70") (name "/DDR_NWE") (class "Default")
      (node (ref "R705") (pin "1") (pinfunction "1_1") (pintype "passive"))
      (node (ref "U300") (pin "M5") (pinfunction "PS_DDR_WE_B_502_M5") (pintype "output"))
    )
    (net (code "71") (name "/DDR_ODT") (class "Default")
      (node (ref "R724") (pin "1") (pinfunction "1_1") (pintype "passive"))
      (node (ref "U300") (pin "N5") (pinfunction "PS_DDR_ODT_502_N5") (pintype "output"))
    )
    (net (code "72") (name "/DDR_VRN") (class "Default")
      (node (ref "R727") (pin "1") (pinfunction "1_1") (pintype "passive"))
      (node (ref "U300") (pin "G5") (pinfunction "PS_DDR_VRN_502_G5") (pintype "output"))
    )
    (net (code "73") (name "/DDR_VRP") (class "Default")
      (node (ref "R729") (pin "2") (pinfunction "2_2") (pintype "passive"))
      (node (ref "U300") (pin "H5") (pinfunction "PS_DDR_VRP_502_H5") (pintype "output"))
    )
    (net (code "74") (name "/DDR_VTT_EN") (class "Default")
      (node (ref "R725") (pin "1") (pinfunction "1_1") (pintype "passive"))
      (node (ref "R730") (pin "2") (pinfunction "2_2") (pintype "passive"))
      (node (ref "U701") (pin "2") (pinfunction "EN_2") (pintype "passive"))
    )
    (net (code "75") (name "/DDR_VTT_VDDQ") (class "Default")
      (node (ref "C717") (pin "2") (pinfunction "2_2") (pintype "passive"))
      (node (ref "R728") (pin "2") (pinfunction "2_2") (pintype "passive"))
      (node (ref "U701") (pin "5") (pinfunction "VDDQ_5") (pintype "passive"))
    )
    (net (code "76") (name "/PG_1.35V") (class "Default")
      (node (ref "R725") (pin "2") (pinfunction "2_2") (pintype "passive"))
    )
    (net (code "77") (name "DGND") (class "Default")
      (node (ref "C700") (pin "1") (pinfunction "1_1") (pintype "passive"))
      (node (ref "C701") (pin "1") (pinfunction "1_1") (pintype "passive"))
      (node (ref "C702") (pin "1") (pinfunction "1_1") (pintype "passive"))
      (node (ref "C703") (pin "1") (pinfunction "1_1") (pintype "passive"))
      (node (ref "C704") (pin "1") (pinfunction "1_1") (pintype "passive"))
      (node (ref "C705") (pin "1") (pinfunction "1_1") (pintype "passive"))
      (node (ref "C706") (pin "1") (pinfunction "1_1") (pintype "passive"))
      (node (ref "C707") (pin "1") (pinfunction "1_1") (pintype "passive"))
      (node (ref "C708") (pin "1") (pinfunction "1_1") (pintype "passive"))
      (node (ref "C709") (pin "1") (pinfunction "1_1") (pintype "passive"))
      (node (ref "C710") (pin "1") (pinfunction "1_1") (pintype "passive"))
      (node (ref "C711") (pin "1") (pinfunction "1_1") (pintype "passive"))
      (node (ref "C712") (pin "1") (pinfunction "1_1") (pintype "passive"))
      (node (ref "C713") (pin "1") (pinfunction "1_1") (pintype "passive"))
      (node (ref "C714") (pin "1") (pinfunction "1_1") (pintype "passive"))
      (node (ref "C715") (pin "1") (pinfunction "1_1") (pintype "passive"))
      (node (ref "C716") (pin "1") (pinfunction "1_1") (pintype "passive"))
      (node (ref "C717") (pin "1") (pinfunction "1_1") (pintype "passive"))
      (node (ref "C718") (pin "1") (pinfunction "1_1") (pintype "passive"))
      (node (ref "C719") (pin "2") (pinfunction "2_2") (pintype "passive"))
      (node (ref "R726") (pin "1") (pinfunction "1_1") (pintype "passive"))
      (node (ref "R729") (pin "1") (pinfunction "1_1") (pintype "passive"))
      (node (ref "R730") (pin "1") (pinfunction "1_1") (pintype "passive"))
      (node (ref "U701") (pin "1") (pinfunction "GND_1") (pintype "passive"))
    )
    (net (code "78") (name "DP0.675VS") (class "Default")
      (node (ref "C700") (pin "2") (pinfunction "2_2") (pintype "passive"))
      (node (ref "C701") (pin "2") (pinfunction "2_2") (pintype "passive"))
      (node (ref "C702") (pin "2") (pinfunction "2_2") (pintype "passive"))
      (node (ref "C703") (pin "2") (pinfunction "2_2") (pintype "passive"))
      (node (ref "C704") (pin "2") (pinfunction "2_2") (pintype "passive"))
      (node (ref "C705") (pin "2") (pinfunction "2_2") (pintype "passive"))
      (node (ref "C706") (pin "2") (pinfunction "2_2") (pintype "passive"))
      (node (ref "C707") (pin "2") (pinfunction "2_2") (pintype "passive"))
      (node (ref "C708") (pin "2") (pinfunction "2_2") (pintype "passive"))
      (node (ref "C709") (pin "2") (pinfunction "2_2") (pintype "passive"))
      (node (ref "C710") (pin "2") (pinfunction "2_2") (pintype "passive"))
      (node (ref "C711") (pin "2") (pinfunction "2_2") (pintype "passive"))
      (node (ref "C712") (pin "2") (pinfunction "2_2") (pintype "passive"))
      (node (ref "C713") (pin "2") (pinfunction "2_2") (pintype "passive"))
      (node (ref "R701") (pin "2") (pinfunction "2_2") (pintype "passive"))
      (node (ref "R702") (pin "2") (pinfunction "2_2") (pintype "passive"))
      (node (ref "R703") (pin "2") (pinfunction "2_2") (pintype "passive"))
      (node (ref "R704") (pin "2") (pinfunction "2_2") (pintype "passive"))
      (node (ref "R705") (pin "2") (pinfunction "2_2") (pintype "passive"))
      (node (ref "R706") (pin "2") (pinfunction "2_2") (pintype "passive"))
      (node (ref "R707") (pin "2") (pinfunction "2_2") (pintype "passive"))
      (node (ref "R708") (pin "2") (pinfunction "2_2") (pintype "passive"))
      (node (ref "R709") (pin "2") (pinfunction "2_2") (pintype "passive"))
      (node (ref "R710") (pin "2") (pinfunction "2_2") (pintype "passive"))
      (node (ref "R711") (pin "2") (pinfunction "2_2") (pintype "passive"))
      (node (ref "R712") (pin "2") (pinfunction "2_2") (pintype "passive"))
      (node (ref "R713") (pin "2") (pinfunction "2_2") (pintype "passive"))
      (node (ref "R714") (pin "2") (pinfunction "2_2") (pintype "passive"))
      (node (ref "R715") (pin "2") (pinfunction "2_2") (pintype "passive"))
      (node (ref "R716") (pin "2") (pinfunction "2_2") (pintype "passive"))
      (node (ref "R717") (pin "2") (pinfunction "2_2") (pintype "passive"))
      (node (ref "R718") (pin "2") (pinfunction "2_2") (pintype "passive"))
      (node (ref "R719") (pin "2") (pinfunction "2_2") (pintype "passive"))
      (node (ref "R720") (pin "2") (pinfunction "2_2") (pintype "passive"))
      (node (ref "R721") (pin "2") (pinfunction "2_2") (pintype "passive"))
      (node (ref "R722") (pin "2") (pinfunction "2_2") (pintype "passive"))
      (node (ref "R723") (pin "2") (pinfunction "2_2") (pintype "passive"))
      (node (ref "R724") (pin "2") (pinfunction "2_2") (pintype "passive"))
      (node (ref "U701") (pin "3") (pinfunction "VTTS_3") (pintype "passive"))
      (node (ref "U701") (pin "8") (pinfunction "VTT_8") (pintype "passive"))
    )
    (net (code "79") (name "DP0.675VS_REF") (class "Default")
      (node (ref "C715") (pin "2") (pinfunction "2_2") (pintype "passive"))
      (node (ref "C716") (pin "2") (pinfunction "2_2") (pintype "passive"))
      (node (ref "C718") (pin "2") (pinfunction "2_2") (pintype "passive"))
      (node (ref "U300") (pin "H6") (pinfunction "PS_DDR_VREF0_502_H6") (pintype "input"))
      (node (ref "U300") (pin "P6") (pinfunction "PS_DDR_VREF1_502_P6") (pintype "input"))
      (node (ref "U701") (pin "4") (pinfunction "VREF_4") (pintype "passive"))
    )
    (net (code "80") (name "DP1.35VS") (class "Default")
      (node (ref "R727") (pin "2") (pinfunction "2_2") (pintype "passive"))
      (node (ref "R728") (pin "1") (pinfunction "1_1") (pintype "passive"))
    )
    (net (code "81") (name "DP5VS") (class "Default")
      (node (ref "C714") (pin "2") (pinfunction "2_2") (pintype "passive"))
      (node (ref "C719") (pin "1") (pinfunction "1_1") (pintype "passive"))
      (node (ref "U701") (pin "6") (pinfunction "VCC_6") (pintype "passive"))
      (node (ref "U701") (pin "7") (pinfunction "VTT_IN_7") (pintype "passive"))
    )
  )
)
